# BME680-Breakout_v10.net
KiCad netlist of a schematic drawn in EAGLE
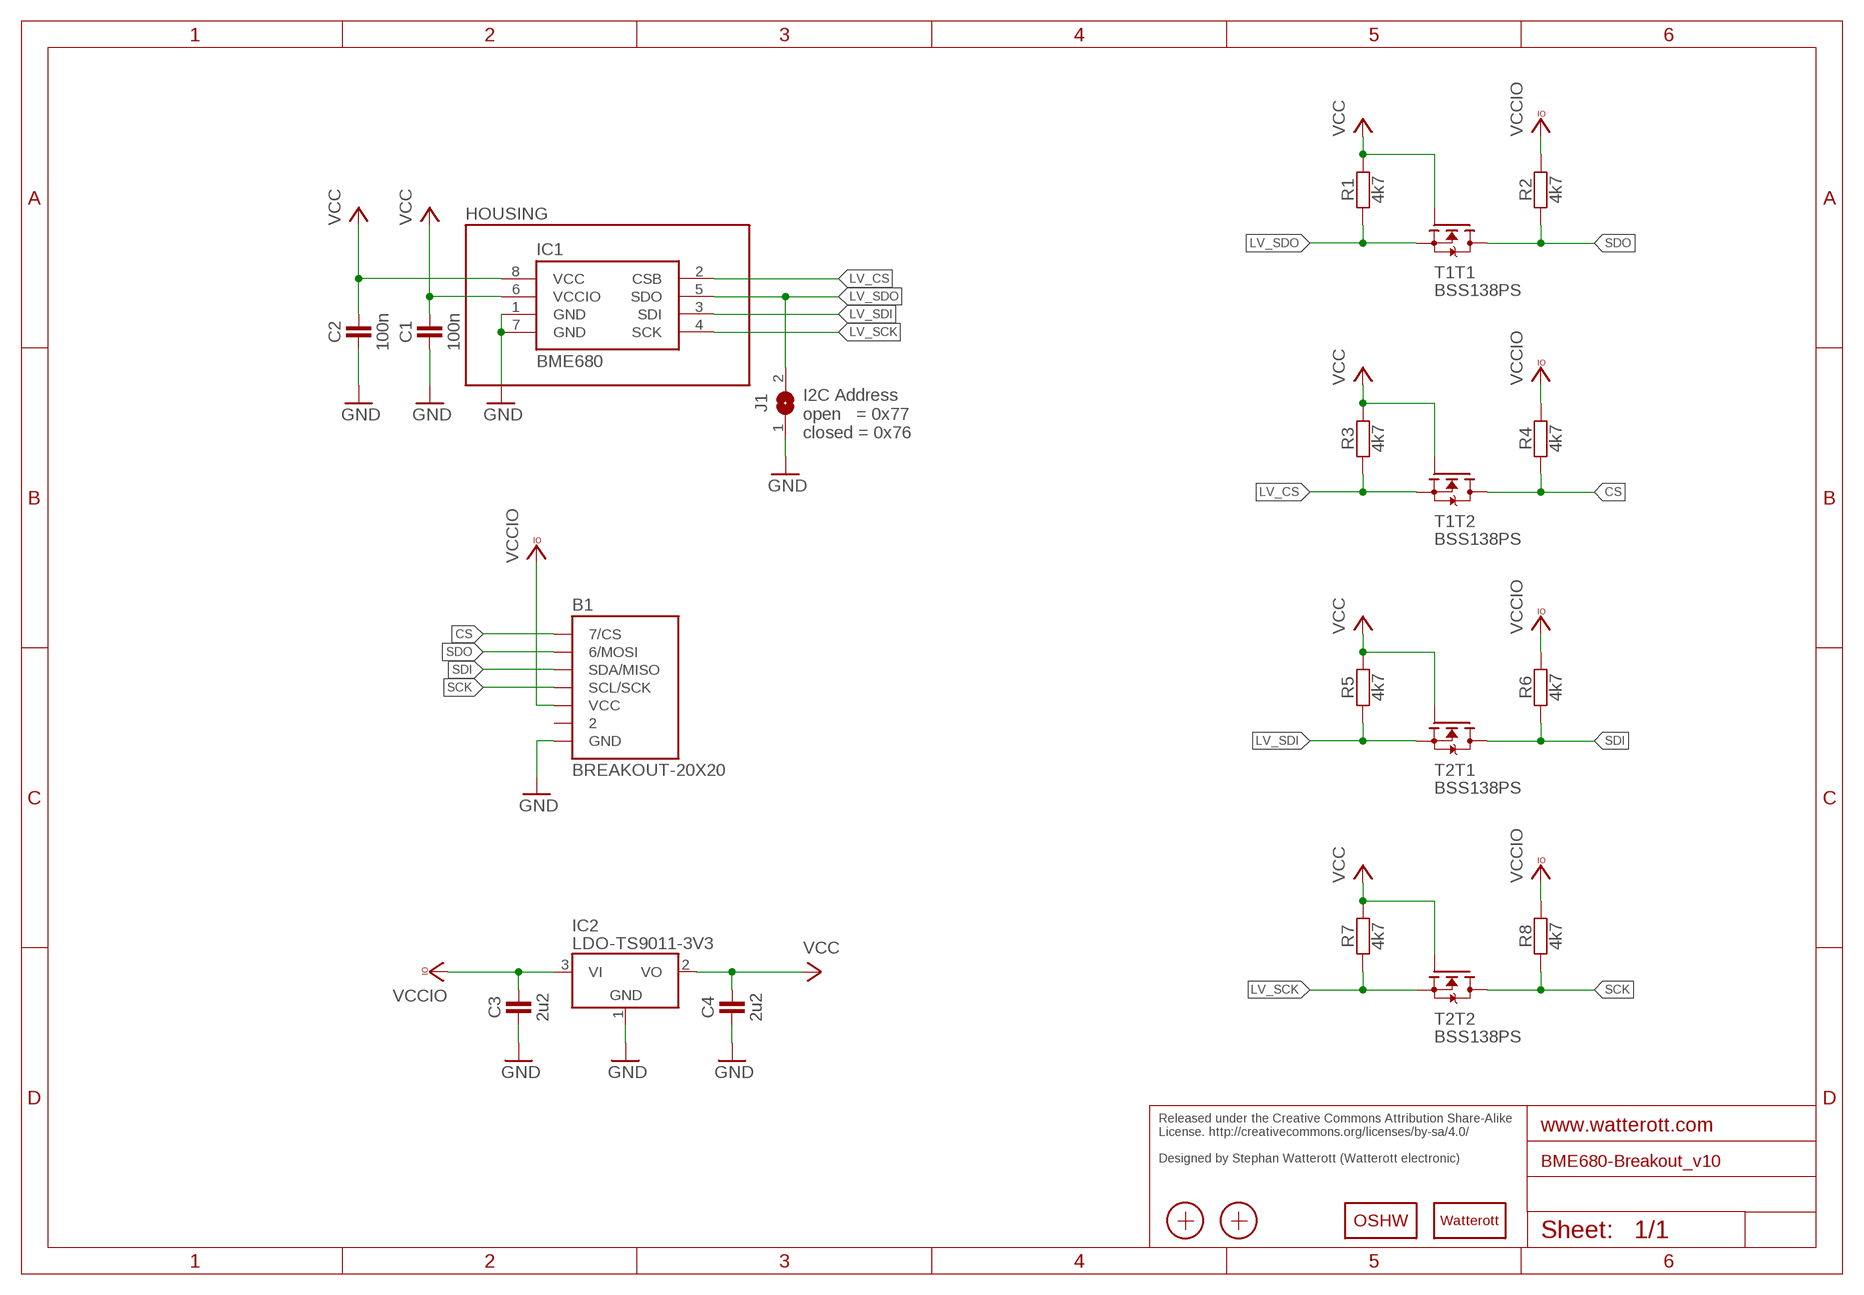
[diagram p0: schematic, sheet 1]

(export (version "E")
  (design (tool "Eeschema 10.0.6"))
  (components
    (comp (ref "B1")
      (value "BREAKOUT-20X20")
      (footprint "eagle-import:BREAKOUT-20X20")
      (libsource (lib "eagle-import") (part "BREAKOUT-20X20"))
    )
    (comp (ref "C1")
      (value "100n")
      (footprint "eagle-import:C0402")
      (libsource (lib "eagle-import") (part "CAPACITOR-0402"))
    )
    (comp (ref "C2")
      (value "100n")
      (footprint "eagle-import:C0402")
      (libsource (lib "eagle-import") (part "CAPACITOR-0402"))
    )
    (comp (ref "C3")
      (value "2u2")
      (footprint "eagle-import:C0402")
      (libsource (lib "eagle-import") (part "CAPACITOR-0402"))
    )
    (comp (ref "C4")
      (value "2u2")
      (footprint "eagle-import:C0402")
      (libsource (lib "eagle-import") (part "CAPACITOR-0402"))
    )
    (comp (ref "HOUSING")
      (value "SF2")
      (footprint "eagle-import:SF2")
      (libsource (lib "eagle-import") (part "SF2"))
    )
    (comp (ref "IC1")
      (value "BME680")
      (footprint "eagle-import:BME680")
      (libsource (lib "eagle-import") (part "BME680"))
    )
    (comp (ref "IC2")
      (value "LDO-TS9011-3V3")
      (footprint "eagle-import:SOT23")
      (libsource (lib "eagle-import") (part "LDO-TS9011-3V3"))
    )
    (comp (ref "J1")
      (value "JUMPER2-0603")
      (footprint "eagle-import:JUMPER2-0603")
      (libsource (lib "eagle-import") (part "JUMPER2-0603"))
    )
    (comp (ref "LOGO1")
      (value "LOGO-S_PLACE_S")
      (footprint "eagle-import:SPARK_TPLACE_S")
      (libsource (lib "eagle-import") (part "LOGO-S_PLACE_S"))
    )
    (comp (ref "LOGO2")
      (value "OSHW_LOGOX0070")
      (footprint "eagle-import:OSHW_6X70")
      (libsource (lib "eagle-import") (part "OSHW_LOGOX0070"))
    )
    (comp (ref "R1")
      (value "4k7")
      (footprint "eagle-import:C0402")
      (libsource (lib "eagle-import") (part "RESISTOR-0402"))
    )
    (comp (ref "R2")
      (value "4k7")
      (footprint "eagle-import:C0402")
      (libsource (lib "eagle-import") (part "RESISTOR-0402"))
    )
    (comp (ref "R3")
      (value "4k7")
      (footprint "eagle-import:C0402")
      (libsource (lib "eagle-import") (part "RESISTOR-0402"))
    )
    (comp (ref "R4")
      (value "4k7")
      (footprint "eagle-import:C0402")
      (libsource (lib "eagle-import") (part "RESISTOR-0402"))
    )
    (comp (ref "R5")
      (value "4k7")
      (footprint "eagle-import:C0402")
      (libsource (lib "eagle-import") (part "RESISTOR-0402"))
    )
    (comp (ref "R6")
      (value "4k7")
      (footprint "eagle-import:C0402")
      (libsource (lib "eagle-import") (part "RESISTOR-0402"))
    )
    (comp (ref "R7")
      (value "4k7")
      (footprint "eagle-import:C0402")
      (libsource (lib "eagle-import") (part "RESISTOR-0402"))
    )
    (comp (ref "R8")
      (value "4k7")
      (footprint "eagle-import:C0402")
      (libsource (lib "eagle-import") (part "RESISTOR-0402"))
    )
    (comp (ref "T1")
      (value "BSS138PS")
      (footprint "eagle-import:SOT363")
      (libsource (lib "eagle-import") (part "BSS138PS"))
    )
    (comp (ref "T2")
      (value "BSS138PS")
      (footprint "eagle-import:SOT363")
      (libsource (lib "eagle-import") (part "BSS138PS"))
    )
    (comp (ref "X1")
      (value "PASSER-07")
      (footprint "eagle-import:PASSER_07MM")
      (libsource (lib "eagle-import") (part "PASSER-07"))
    )
    (comp (ref "X2")
      (value "PASSER-07")
      (footprint "eagle-import:PASSER_07MM")
      (libsource (lib "eagle-import") (part "PASSER-07"))
    )
  )
  (nets
    (net (code "1") (name "CS") (class "Default")
      (node (ref "B1") (pin "CS") (pinfunction "7/CS_CS") (pintype "bidirectional"))
      (node (ref "R4") (pin "1") (pinfunction "1_1") (pintype "passive"))
      (node (ref "T1") (pin "3") (pinfunction "D_3") (pintype "passive"))
    )
    (net (code "2") (name "GND") (class "Default")
      (node (ref "B1") (pin "GND") (pinfunction "GND_GND") (pintype "power_in"))
      (node (ref "C1") (pin "1") (pinfunction "1_1") (pintype "passive"))
      (node (ref "C2") (pin "1") (pinfunction "1_1") (pintype "passive"))
      (node (ref "C3") (pin "1") (pinfunction "1_1") (pintype "passive"))
      (node (ref "C4") (pin "1") (pinfunction "1_1") (pintype "passive"))
      (node (ref "IC1") (pin "1") (pinfunction "GND_1") (pintype "power_in"))
      (node (ref "IC1") (pin "7") (pinfunction "GND_7") (pintype "power_in"))
      (node (ref "IC2") (pin "1") (pinfunction "GND_1") (pintype "passive"))
      (node (ref "J1") (pin "1") (pinfunction "1_1") (pintype "passive"))
    )
    (net (code "3") (name "LV_CS") (class "Default")
      (node (ref "IC1") (pin "2") (pinfunction "CSB_2") (pintype "input"))
      (node (ref "R3") (pin "1") (pinfunction "1_1") (pintype "passive"))
      (node (ref "T1") (pin "4") (pinfunction "S_4") (pintype "passive"))
    )
    (net (code "4") (name "LV_SCK") (class "Default")
      (node (ref "IC1") (pin "4") (pinfunction "SCK_4") (pintype "bidirectional"))
      (node (ref "R7") (pin "1") (pinfunction "1_1") (pintype "passive"))
      (node (ref "T2") (pin "4") (pinfunction "S_4") (pintype "passive"))
    )
    (net (code "5") (name "LV_SDI") (class "Default")
      (node (ref "IC1") (pin "3") (pinfunction "SDI_3") (pintype "bidirectional"))
      (node (ref "R5") (pin "1") (pinfunction "1_1") (pintype "passive"))
      (node (ref "T2") (pin "1") (pinfunction "S_1") (pintype "passive"))
    )
    (net (code "6") (name "LV_SDO") (class "Default")
      (node (ref "IC1") (pin "5") (pinfunction "SDO_5") (pintype "bidirectional"))
      (node (ref "J1") (pin "2") (pinfunction "2_2") (pintype "passive"))
      (node (ref "R1") (pin "1") (pinfunction "1_1") (pintype "passive"))
      (node (ref "T1") (pin "1") (pinfunction "S_1") (pintype "passive"))
    )
    (net (code "7") (name "SCK") (class "Default")
      (node (ref "B1") (pin "SCL/SCK") (pinfunction "SCL/SCK_SCL/SCK") (pintype "bidirectional"))
      (node (ref "R8") (pin "1") (pinfunction "1_1") (pintype "passive"))
      (node (ref "T2") (pin "3") (pinfunction "D_3") (pintype "passive"))
    )
    (net (code "8") (name "SDI") (class "Default")
      (node (ref "B1") (pin "SDA/MISO") (pinfunction "SDA/MISO_SDA/MISO") (pintype "bidirectional"))
      (node (ref "R6") (pin "1") (pinfunction "1_1") (pintype "passive"))
      (node (ref "T2") (pin "6") (pinfunction "D_6") (pintype "passive"))
    )
    (net (code "9") (name "SDO") (class "Default")
      (node (ref "B1") (pin "MOSI") (pinfunction "6/MOSI_MOSI") (pintype "bidirectional"))
      (node (ref "R2") (pin "1") (pinfunction "1_1") (pintype "passive"))
      (node (ref "T1") (pin "6") (pinfunction "D_6") (pintype "passive"))
    )
    (net (code "10") (name "VCC") (class "Default")
      (node (ref "C1") (pin "2") (pinfunction "2_2") (pintype "passive"))
      (node (ref "C2") (pin "2") (pinfunction "2_2") (pintype "passive"))
      (node (ref "C4") (pin "2") (pinfunction "2_2") (pintype "passive"))
      (node (ref "IC1") (pin "6") (pinfunction "VCCIO_6") (pintype "power_in"))
      (node (ref "IC1") (pin "8") (pinfunction "VCC_8") (pintype "power_in"))
      (node (ref "IC2") (pin "2") (pinfunction "VO_2") (pintype "passive"))
      (node (ref "R1") (pin "2") (pinfunction "2_2") (pintype "passive"))
      (node (ref "R3") (pin "2") (pinfunction "2_2") (pintype "passive"))
      (node (ref "R5") (pin "2") (pinfunction "2_2") (pintype "passive"))
      (node (ref "R7") (pin "2") (pinfunction "2_2") (pintype "passive"))
      (node (ref "T1") (pin "2") (pinfunction "G_2") (pintype "passive"))
      (node (ref "T1") (pin "5") (pinfunction "G_5") (pintype "passive"))
      (node (ref "T2") (pin "2") (pinfunction "G_2") (pintype "passive"))
      (node (ref "T2") (pin "5") (pinfunction "G_5") (pintype "passive"))
    )
    (net (code "11") (name "VCCIO") (class "Default")
      (node (ref "B1") (pin "VCC") (pinfunction "VCC_VCC") (pintype "power_in"))
      (node (ref "C3") (pin "2") (pinfunction "2_2") (pintype "passive"))
      (node (ref "IC2") (pin "3") (pinfunction "VI_3") (pintype "input"))
      (node (ref "R2") (pin "2") (pinfunction "2_2") (pintype "passive"))
      (node (ref "R4") (pin "2") (pinfunction "2_2") (pintype "passive"))
      (node (ref "R6") (pin "2") (pinfunction "2_2") (pintype "passive"))
      (node (ref "R8") (pin "2") (pinfunction "2_2") (pintype "passive"))
    )
    (net (code "12") (name "unconnected-(B1-Pad2)") (class "Default")
      (node (ref "B1") (pin "2") (pinfunction "2_2") (pintype "bidirectional"))
    )
  )
)
